# MySens-easyRS485-v002.net
KiCad netlist of a schematic drawn in EAGLE
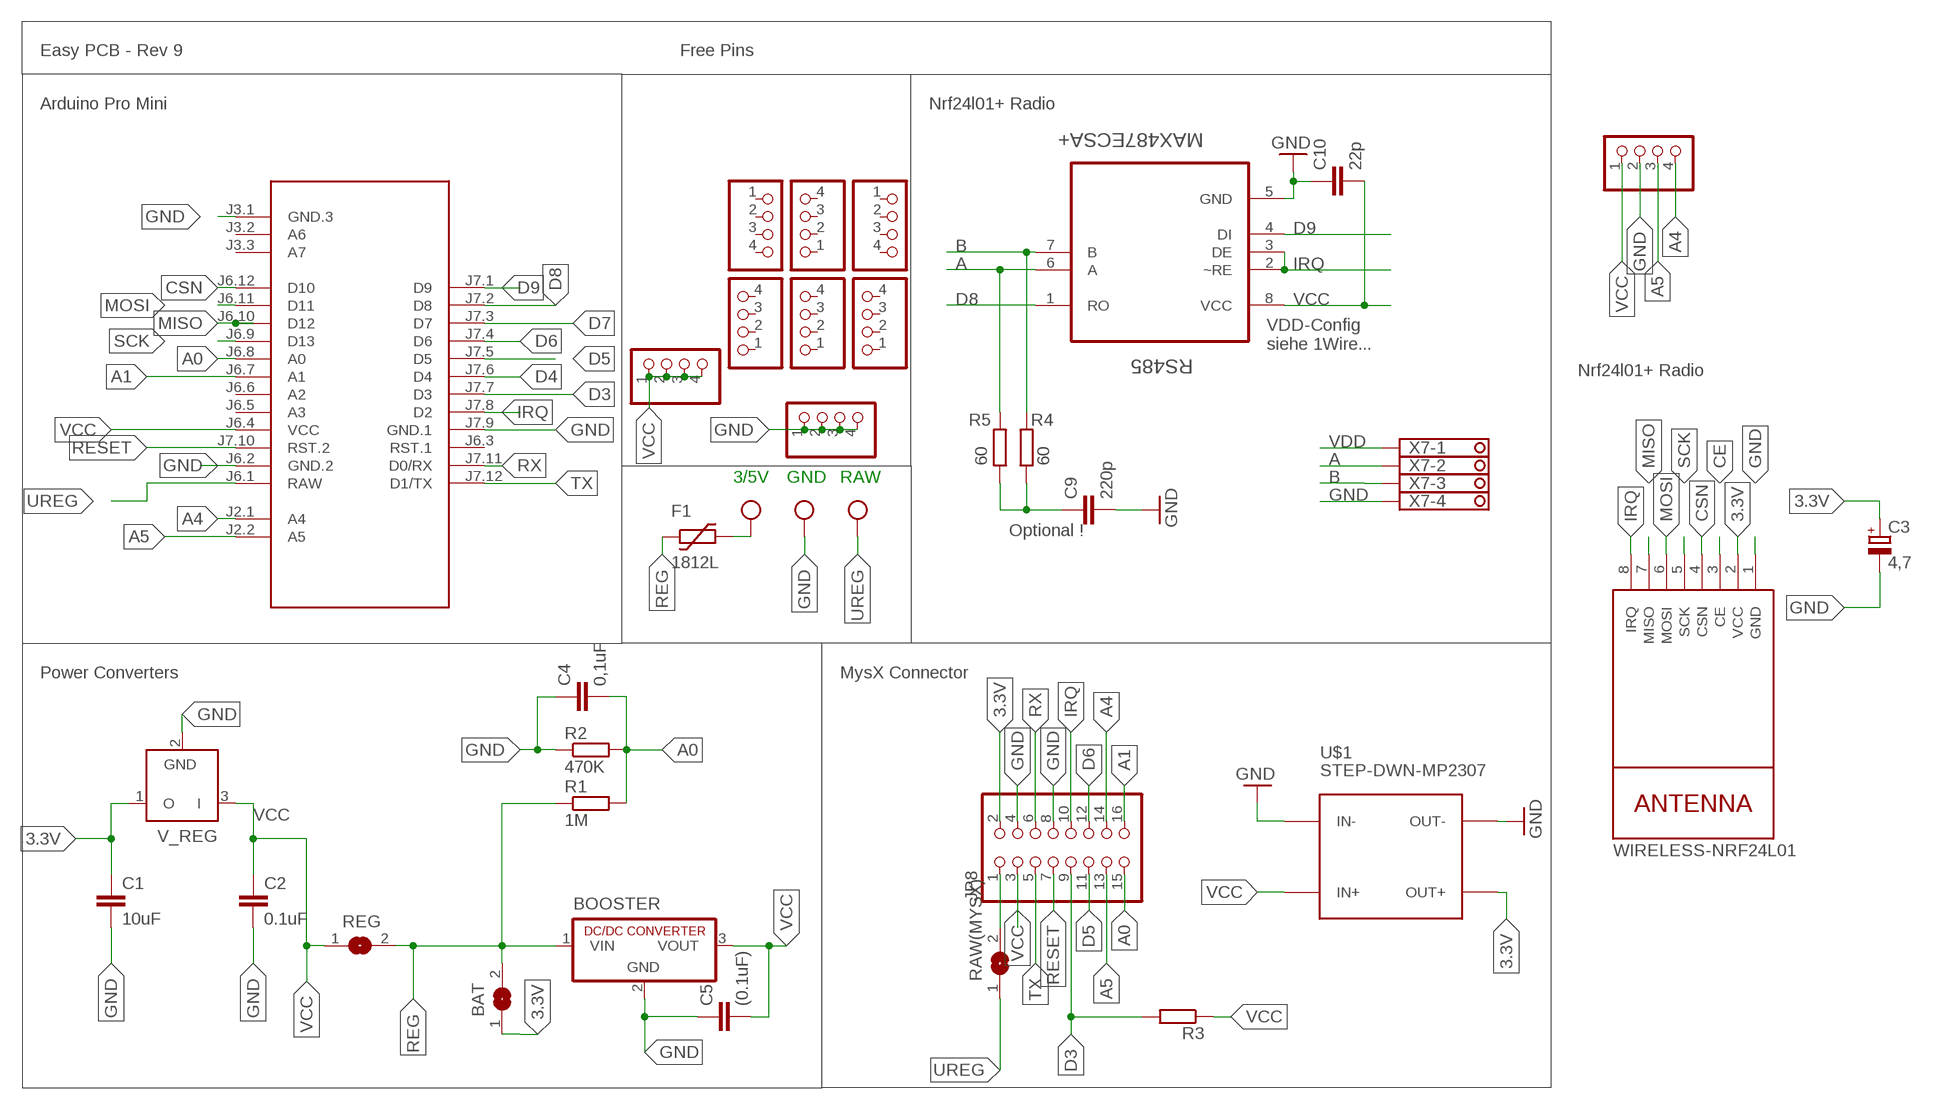
[diagram p0: schematic, sheet 1]

(export (version "E")
  (design (tool "Eeschema 10.0.6"))
  (components
    (comp (ref ".")
      (value "W237-103")
      (footprint "eagle-import:W237-103")
      (fields (field (name "MPN") "237-103"))
      (libsource (lib "eagle-import") (part "W237-103"))
    )
    (comp (ref "BAT") (value "SJ") (footprint "eagle-import:SJ") (libsource (lib "eagle-import") (part "SJ")))
    (comp (ref "BOOSTER")
      (value "R-78C1.8-1.0")
      (footprint "eagle-import:SIP3")
      (libsource (lib "eagle-import") (part "R-78C-1.01.8"))
    )
    (comp (ref "C1")
      (value "10uF")
      (footprint "eagle-import:C1210")
      (libsource (lib "eagle-import") (part "C-EUC1210"))
    )
    (comp (ref "C2")
      (value "0.1uF")
      (footprint "eagle-import:C1206")
      (libsource (lib "eagle-import") (part "C-EUC1206"))
    )
    (comp (ref "C3")
      (value "4,7")
      (footprint "eagle-import:SMC_C")
      (libsource (lib "eagle-import") (part "CPOL-EUSMCC"))
    )
    (comp (ref "C4")
      (value "0,1uF")
      (footprint "eagle-import:C1206")
      (libsource (lib "eagle-import") (part "C-EUC1206"))
    )
    (comp (ref "C5")
      (value "(0.1uF)")
      (footprint "eagle-import:C1206")
      (libsource (lib "eagle-import") (part "C-EUC1206"))
    )
    (comp (ref "C9")
      (value "220p")
      (footprint "eagle-import:C0805")
      (libsource (lib "eagle-import") (part "C-EUC0805"))
    )
    (comp (ref "C10")
      (value "22p")
      (footprint "eagle-import:C0805")
      (libsource (lib "eagle-import") (part "C-EUC0805"))
    )
    (comp (ref "F1")
      (value "1812L")
      (footprint "eagle-import:1812L")
      (libsource (lib "eagle-import") (part "1812L"))
    )
    (comp (ref "JP1")
      (value "PINHD-1X04_2.54-S")
      (footprint "eagle-import:1X04-S")
      (libsource (lib "eagle-import") (part "PINHD-1X04_2.54-S"))
    )
    (comp (ref "JP3")
      (value "PINHD-1X04_2.54-S")
      (footprint "eagle-import:1X04-S")
      (libsource (lib "eagle-import") (part "PINHD-1X04_2.54-S"))
    )
    (comp (ref "JP5")
      (value "PINHD-1X04_2.54-S")
      (footprint "eagle-import:1X04-S")
      (libsource (lib "eagle-import") (part "PINHD-1X04_2.54-S"))
    )
    (comp (ref "JP8")
      (value "PINHD-2X08_2.54")
      (footprint "eagle-import:2X08")
      (libsource (lib "eagle-import") (part "PINHD-2X08_2.54"))
    )
    (comp (ref "JP10")
      (value "PINHD-1X04_2.54-S")
      (footprint "eagle-import:1X04-S")
      (libsource (lib "eagle-import") (part "PINHD-1X04_2.54-S"))
    )
    (comp (ref "JP11")
      (value "PINHD-1X04_2.54-S")
      (footprint "eagle-import:1X04-S")
      (libsource (lib "eagle-import") (part "PINHD-1X04_2.54-S"))
    )
    (comp (ref "JP12")
      (value "PINHD-1X04_2.54-S")
      (footprint "eagle-import:1X04-S")
      (libsource (lib "eagle-import") (part "PINHD-1X04_2.54-S"))
    )
    (comp (ref "JP14")
      (value "PINHD-1X04_2.54-S")
      (footprint "eagle-import:1X04-S")
      (libsource (lib "eagle-import") (part "PINHD-1X04_2.54-S"))
    )
    (comp (ref "JP15")
      (value "PINHD-1X04_2.54-S")
      (footprint "eagle-import:1X04-S")
      (libsource (lib "eagle-import") (part "PINHD-1X04_2.54-S"))
    )
    (comp (ref "JP16")
      (value "PINHD-1X04_2.54-S")
      (footprint "eagle-import:1X04-S")
      (libsource (lib "eagle-import") (part "PINHD-1X04_2.54-S"))
    )
    (comp (ref "M1")
      (value "ARDUINO-PRO-MINI-3.3V#NP")
      (footprint "eagle-import:ARDUINO-PRO-MINI#NP")
      (libsource (lib "eagle-import") (part "ARDUINO-PRO-MINI-#NP3.3V"))
    )
    (comp (ref "NRF24L01+")
      (value "WIRELESS-NRF24L01")
      (footprint "eagle-import:WIRELESS-NRF24L01")
      (libsource (lib "eagle-import") (part "WIRELESS-NRF24L01"))
    )
    (comp (ref "R1")
      (value "1M")
      (footprint "eagle-import:R0805")
      (libsource (lib "eagle-import") (part "R-EU_R0805"))
    )
    (comp (ref "R2")
      (value "470K")
      (footprint "eagle-import:R0805")
      (libsource (lib "eagle-import") (part "R-EU_R0805"))
    )
    (comp (ref "R3")
      (value "R-EU_R0805")
      (footprint "eagle-import:R0805")
      (libsource (lib "eagle-import") (part "R-EU_R0805"))
    )
    (comp (ref "R4")
      (value "60")
      (footprint "eagle-import:R0805")
      (libsource (lib "eagle-import") (part "R-EU_R0805"))
    )
    (comp (ref "R5")
      (value "60")
      (footprint "eagle-import:R0805")
      (libsource (lib "eagle-import") (part "R-EU_R0805"))
    )
    (comp (ref "RAW(MYSX)")
      (value "SJ")
      (footprint "eagle-import:SJ")
      (libsource (lib "eagle-import") (part "SJ"))
    )
    (comp (ref "REG") (value "SJ") (footprint "eagle-import:SJ") (libsource (lib "eagle-import") (part "SJ")))
    (comp (ref "RS485")
      (value "MAX487ECSA+")
      (footprint "eagle-import:SOIC127P600X175-8N")
      (libsource (lib "eagle-import") (part "MAX487ECSA+"))
    )
    (comp (ref "U$1")
      (value "STEP-DWN-MP2307")
      (footprint "eagle-import:DC-DC-STEP-DOWN-MP2307")
      (libsource (lib "eagle-import") (part "DC-DC-STEP-DOWN-MP2307"))
    )
    (comp (ref "V_REG")
      (value "LP2950Z")
      (footprint "eagle-import:TO92")
      (libsource (lib "eagle-import") (part "LP2950Z"))
    )
    (comp (ref "X7")
      (value "1751264")
      (footprint "eagle-import:1751264")
      (libsource (lib "eagle-import") (part "1751264"))
    )
  )
  (nets
    (net (code "1") (name "/A") (class "Default")
      (node (ref "R5") (pin "2") (pinfunction "2_2") (pintype "passive"))
      (node (ref "RS485") (pin "6") (pinfunction "A_6") (pintype "bidirectional"))
      (node (ref "X7") (pin "2") (pinfunction "K_2") (pintype "passive"))
    )
    (net (code "2") (name "/B") (class "Default")
      (node (ref "R4") (pin "2") (pinfunction "2_2") (pintype "passive"))
      (node (ref "RS485") (pin "7") (pinfunction "B_7") (pintype "bidirectional"))
      (node (ref "X7") (pin "3") (pinfunction "K_3") (pintype "passive"))
    )
    (net (code "3") (name "/VDD") (class "Default")
      (node (ref "X7") (pin "1") (pinfunction "K_1") (pintype "passive"))
    )
    (net (code "4") (name "3.3V") (class "Default")
      (node (ref "BAT") (pin "1") (pinfunction "1_1") (pintype "passive"))
      (node (ref "C1") (pin "1") (pinfunction "1_1") (pintype "passive"))
      (node (ref "C3") (pin "+") (pinfunction "+_+") (pintype "passive"))
      (node (ref "JP8") (pin "2") (pinfunction "2_2") (pintype "passive"))
      (node (ref "NRF24L01+") (pin "2") (pinfunction "VCC_2") (pintype "power_in"))
      (node (ref "U$1") (pin "OUT+") (pinfunction "OUT+_OUT+") (pintype "bidirectional"))
      (node (ref "V_REG") (pin "1") (pinfunction "O_1") (pintype "input"))
    )
    (net (code "5") (name "A0") (class "Default")
      (node (ref "C4") (pin "2") (pinfunction "2_2") (pintype "passive"))
      (node (ref "JP8") (pin "15") (pinfunction "15_15") (pintype "passive"))
      (node (ref "M1") (pin "J6.8") (pinfunction "A0_J6.8") (pintype "bidirectional"))
      (node (ref "R1") (pin "2") (pinfunction "2_2") (pintype "passive"))
      (node (ref "R2") (pin "2") (pinfunction "2_2") (pintype "passive"))
    )
    (net (code "6") (name "A1") (class "Default")
      (node (ref "JP8") (pin "16") (pinfunction "16_16") (pintype "passive"))
      (node (ref "M1") (pin "J6.7") (pinfunction "A1_J6.7") (pintype "bidirectional"))
    )
    (net (code "7") (name "A4") (class "Default")
      (node (ref "JP10") (pin "4") (pinfunction "4_4") (pintype "passive"))
      (node (ref "JP8") (pin "14") (pinfunction "14_14") (pintype "passive"))
      (node (ref "M1") (pin "J2.1") (pinfunction "A4_J2.1") (pintype "bidirectional"))
    )
    (net (code "8") (name "A5") (class "Default")
      (node (ref "JP10") (pin "3") (pinfunction "3_3") (pintype "passive"))
      (node (ref "JP8") (pin "13") (pinfunction "13_13") (pintype "passive"))
      (node (ref "M1") (pin "J2.2") (pinfunction "A5_J2.2") (pintype "bidirectional"))
    )
    (net (code "9") (name "CE") (class "Default")
      (node (ref "NRF24L01+") (pin "3") (pinfunction "CE_3") (pintype "bidirectional"))
    )
    (net (code "10") (name "CSN") (class "Default")
      (node (ref "M1") (pin "J6.12") (pinfunction "D10_J6.12") (pintype "bidirectional"))
      (node (ref "NRF24L01+") (pin "4") (pinfunction "CSN_4") (pintype "bidirectional"))
    )
    (net (code "11") (name "D3") (class "Default")
      (node (ref "JP8") (pin "9") (pinfunction "9_9") (pintype "passive"))
      (node (ref "M1") (pin "J7.7") (pinfunction "D3_J7.7") (pintype "bidirectional"))
      (node (ref "R3") (pin "2") (pinfunction "2_2") (pintype "passive"))
    )
    (net (code "12") (name "D4") (class "Default")
      (node (ref "M1") (pin "J7.6") (pinfunction "D4_J7.6") (pintype "bidirectional"))
    )
    (net (code "13") (name "D5") (class "Default")
      (node (ref "JP8") (pin "11") (pinfunction "11_11") (pintype "passive"))
      (node (ref "M1") (pin "J7.5") (pinfunction "D5_J7.5") (pintype "bidirectional"))
    )
    (net (code "14") (name "D6") (class "Default")
      (node (ref "JP8") (pin "12") (pinfunction "12_12") (pintype "passive"))
      (node (ref "M1") (pin "J7.4") (pinfunction "D6_J7.4") (pintype "bidirectional"))
    )
    (net (code "15") (name "D7") (class "Default")
      (node (ref "M1") (pin "J7.3") (pinfunction "D7_J7.3") (pintype "bidirectional"))
    )
    (net (code "16") (name "D8") (class "Default")
      (node (ref "M1") (pin "J7.2") (pinfunction "D8_J7.2") (pintype "bidirectional"))
      (node (ref "RS485") (pin "1") (pinfunction "RO_1") (pintype "output"))
    )
    (net (code "17") (name "D9") (class "Default")
      (node (ref "M1") (pin "J7.1") (pinfunction "D9_J7.1") (pintype "bidirectional"))
      (node (ref "RS485") (pin "4") (pinfunction "DI_4") (pintype "input"))
    )
    (net (code "18") (name "GND") (class "Default")
      (node (ref ".") (pin "2") (pinfunction "KL_2") (pintype "passive"))
      (node (ref "BOOSTER") (pin "2") (pinfunction "GND_2") (pintype "passive"))
      (node (ref "C1") (pin "2") (pinfunction "2_2") (pintype "passive"))
      (node (ref "C10") (pin "1") (pinfunction "1_1") (pintype "passive"))
      (node (ref "C2") (pin "2") (pinfunction "2_2") (pintype "passive"))
      (node (ref "C3") (pin "-") (pinfunction "-_-") (pintype "passive"))
      (node (ref "C4") (pin "1") (pinfunction "1_1") (pintype "passive"))
      (node (ref "C5") (pin "1") (pinfunction "1_1") (pintype "passive"))
      (node (ref "C9") (pin "2") (pinfunction "2_2") (pintype "passive"))
      (node (ref "JP1") (pin "1") (pinfunction "1_1") (pintype "passive"))
      (node (ref "JP1") (pin "2") (pinfunction "2_2") (pintype "passive"))
      (node (ref "JP1") (pin "3") (pinfunction "3_3") (pintype "passive"))
      (node (ref "JP1") (pin "4") (pinfunction "4_4") (pintype "passive"))
      (node (ref "JP10") (pin "2") (pinfunction "2_2") (pintype "passive"))
      (node (ref "JP8") (pin "4") (pinfunction "4_4") (pintype "passive"))
      (node (ref "JP8") (pin "8") (pinfunction "8_8") (pintype "passive"))
      (node (ref "M1") (pin "J3.1") (pinfunction "GND.3_J3.1") (pintype "bidirectional"))
      (node (ref "M1") (pin "J6.2") (pinfunction "GND.2_J6.2") (pintype "power_in"))
      (node (ref "M1") (pin "J7.9") (pinfunction "GND.1_J7.9") (pintype "power_in"))
      (node (ref "NRF24L01+") (pin "1") (pinfunction "GND_1") (pintype "power_in"))
      (node (ref "R2") (pin "1") (pinfunction "1_1") (pintype "passive"))
      (node (ref "RS485") (pin "5") (pinfunction "GND_5") (pintype "passive"))
      (node (ref "U$1") (pin "IN-") (pinfunction "IN-_IN-") (pintype "bidirectional"))
      (node (ref "U$1") (pin "OUT-") (pinfunction "OUT-_OUT-") (pintype "bidirectional"))
      (node (ref "V_REG") (pin "2") (pinfunction "GND_2") (pintype "power_in"))
      (node (ref "X7") (pin "4") (pinfunction "K_4") (pintype "passive"))
    )
    (net (code "19") (name "IRQ") (class "Default")
      (node (ref "JP8") (pin "10") (pinfunction "10_10") (pintype "passive"))
      (node (ref "M1") (pin "J7.8") (pinfunction "D2_J7.8") (pintype "bidirectional"))
      (node (ref "NRF24L01+") (pin "8") (pinfunction "IRQ_8") (pintype "bidirectional"))
      (node (ref "RS485") (pin "2") (pinfunction "~{RE}_2") (pintype "input"))
      (node (ref "RS485") (pin "3") (pinfunction "DE_3") (pintype "input"))
    )
    (net (code "20") (name "MISO") (class "Default")
      (node (ref "M1") (pin "J6.10") (pinfunction "D12_J6.10") (pintype "bidirectional"))
      (node (ref "NRF24L01+") (pin "7") (pinfunction "MISO_7") (pintype "bidirectional"))
    )
    (net (code "21") (name "MOSI") (class "Default")
      (node (ref "M1") (pin "J6.11") (pinfunction "D11_J6.11") (pintype "bidirectional"))
      (node (ref "NRF24L01+") (pin "6") (pinfunction "MOSI_6") (pintype "bidirectional"))
    )
    (net (code "22") (name "Net-(.C-KL)") (class "Default")
      (node (ref ".") (pin "3") (pinfunction "KL_3") (pintype "passive"))
      (node (ref "F1") (pin "P$2") (pinfunction "2_P$2") (pintype "passive"))
    )
    (net (code "23") (name "Net-(C9-Pad1)") (class "Default")
      (node (ref "C9") (pin "1") (pinfunction "1_1") (pintype "passive"))
      (node (ref "R4") (pin "1") (pinfunction "1_1") (pintype "passive"))
      (node (ref "R5") (pin "1") (pinfunction "1_1") (pintype "passive"))
    )
    (net (code "24") (name "Net-(JP8-Pad1)") (class "Default")
      (node (ref "JP8") (pin "1") (pinfunction "1_1") (pintype "passive"))
      (node (ref "RAW(MYSX)") (pin "2") (pinfunction "2_2") (pintype "passive"))
    )
    (net (code "25") (name "REG") (class "Default")
      (node (ref "BAT") (pin "2") (pinfunction "2_2") (pintype "passive"))
      (node (ref "BOOSTER") (pin "1") (pinfunction "VIN_1") (pintype "passive"))
      (node (ref "F1") (pin "P$1") (pinfunction "1_P$1") (pintype "passive"))
      (node (ref "R1") (pin "1") (pinfunction "1_1") (pintype "passive"))
      (node (ref "REG") (pin "2") (pinfunction "2_2") (pintype "passive"))
    )
    (net (code "26") (name "RESET") (class "Default")
      (node (ref "JP8") (pin "7") (pinfunction "7_7") (pintype "passive"))
      (node (ref "M1") (pin "J7.10") (pinfunction "RST.2_J7.10") (pintype "bidirectional"))
    )
    (net (code "27") (name "RX") (class "Default")
      (node (ref "JP8") (pin "6") (pinfunction "6_6") (pintype "passive"))
      (node (ref "M1") (pin "J7.11") (pinfunction "D0/RX_J7.11") (pintype "bidirectional"))
    )
    (net (code "28") (name "SCK") (class "Default")
      (node (ref "M1") (pin "J6.9") (pinfunction "D13_J6.9") (pintype "bidirectional"))
      (node (ref "NRF24L01+") (pin "5") (pinfunction "SCK_5") (pintype "bidirectional"))
    )
    (net (code "29") (name "TX") (class "Default")
      (node (ref "JP8") (pin "5") (pinfunction "5_5") (pintype "passive"))
      (node (ref "M1") (pin "J7.12") (pinfunction "D1/TX_J7.12") (pintype "bidirectional"))
    )
    (net (code "30") (name "UREG") (class "Default")
      (node (ref ".") (pin "1") (pinfunction "KL_1") (pintype "passive"))
      (node (ref "M1") (pin "J6.1") (pinfunction "RAW_J6.1") (pintype "power_in"))
      (node (ref "RAW(MYSX)") (pin "1") (pinfunction "1_1") (pintype "passive"))
    )
    (net (code "31") (name "VCC") (class "Default")
      (node (ref "BOOSTER") (pin "3") (pinfunction "VOUT_3") (pintype "passive"))
      (node (ref "C10") (pin "2") (pinfunction "2_2") (pintype "passive"))
      (node (ref "C2") (pin "1") (pinfunction "1_1") (pintype "passive"))
      (node (ref "C5") (pin "2") (pinfunction "2_2") (pintype "passive"))
      (node (ref "JP10") (pin "1") (pinfunction "1_1") (pintype "passive"))
      (node (ref "JP3") (pin "1") (pinfunction "1_1") (pintype "passive"))
      (node (ref "JP3") (pin "2") (pinfunction "2_2") (pintype "passive"))
      (node (ref "JP3") (pin "3") (pinfunction "3_3") (pintype "passive"))
      (node (ref "JP3") (pin "4") (pinfunction "4_4") (pintype "passive"))
      (node (ref "JP8") (pin "3") (pinfunction "3_3") (pintype "passive"))
      (node (ref "M1") (pin "J6.4") (pinfunction "VCC_J6.4") (pintype "power_in"))
      (node (ref "R3") (pin "1") (pinfunction "1_1") (pintype "passive"))
      (node (ref "REG") (pin "1") (pinfunction "1_1") (pintype "passive"))
      (node (ref "RS485") (pin "8") (pinfunction "VCC_8") (pintype "power_in"))
      (node (ref "U$1") (pin "IN+") (pinfunction "IN+_IN+") (pintype "bidirectional"))
      (node (ref "V_REG") (pin "3") (pinfunction "I_3") (pintype "input"))
    )
    (net (code "32") (name "unconnected-(JP5-Pad1)") (class "Default")
      (node (ref "JP5") (pin "1") (pinfunction "1_1") (pintype "passive"))
    )
    (net (code "33") (name "unconnected-(JP5-Pad2)") (class "Default")
      (node (ref "JP5") (pin "2") (pinfunction "2_2") (pintype "passive"))
    )
    (net (code "34") (name "unconnected-(JP5-Pad3)") (class "Default")
      (node (ref "JP5") (pin "3") (pinfunction "3_3") (pintype "passive"))
    )
    (net (code "35") (name "unconnected-(JP5-Pad4)") (class "Default")
      (node (ref "JP5") (pin "4") (pinfunction "4_4") (pintype "passive"))
    )
    (net (code "36") (name "unconnected-(JP11-Pad1)") (class "Default")
      (node (ref "JP11") (pin "1") (pinfunction "1_1") (pintype "passive"))
    )
    (net (code "37") (name "unconnected-(JP11-Pad2)") (class "Default")
      (node (ref "JP11") (pin "2") (pinfunction "2_2") (pintype "passive"))
    )
    (net (code "38") (name "unconnected-(JP11-Pad3)") (class "Default")
      (node (ref "JP11") (pin "3") (pinfunction "3_3") (pintype "passive"))
    )
    (net (code "39") (name "unconnected-(JP11-Pad4)") (class "Default")
      (node (ref "JP11") (pin "4") (pinfunction "4_4") (pintype "passive"))
    )
    (net (code "40") (name "unconnected-(JP12-Pad1)") (class "Default")
      (node (ref "JP12") (pin "1") (pinfunction "1_1") (pintype "passive"))
    )
    (net (code "41") (name "unconnected-(JP12-Pad2)") (class "Default")
      (node (ref "JP12") (pin "2") (pinfunction "2_2") (pintype "passive"))
    )
    (net (code "42") (name "unconnected-(JP12-Pad3)") (class "Default")
      (node (ref "JP12") (pin "3") (pinfunction "3_3") (pintype "passive"))
    )
    (net (code "43") (name "unconnected-(JP12-Pad4)") (class "Default")
      (node (ref "JP12") (pin "4") (pinfunction "4_4") (pintype "passive"))
    )
    (net (code "44") (name "unconnected-(JP14-Pad1)") (class "Default")
      (node (ref "JP14") (pin "1") (pinfunction "1_1") (pintype "passive"))
    )
    (net (code "45") (name "unconnected-(JP14-Pad2)") (class "Default")
      (node (ref "JP14") (pin "2") (pinfunction "2_2") (pintype "passive"))
    )
    (net (code "46") (name "unconnected-(JP14-Pad3)") (class "Default")
      (node (ref "JP14") (pin "3") (pinfunction "3_3") (pintype "passive"))
    )
    (net (code "47") (name "unconnected-(JP14-Pad4)") (class "Default")
      (node (ref "JP14") (pin "4") (pinfunction "4_4") (pintype "passive"))
    )
    (net (code "48") (name "unconnected-(JP15-Pad1)") (class "Default")
      (node (ref "JP15") (pin "1") (pinfunction "1_1") (pintype "passive"))
    )
    (net (code "49") (name "unconnected-(JP15-Pad2)") (class "Default")
      (node (ref "JP15") (pin "2") (pinfunction "2_2") (pintype "passive"))
    )
    (net (code "50") (name "unconnected-(JP15-Pad3)") (class "Default")
      (node (ref "JP15") (pin "3") (pinfunction "3_3") (pintype "passive"))
    )
    (net (code "51") (name "unconnected-(JP15-Pad4)") (class "Default")
      (node (ref "JP15") (pin "4") (pinfunction "4_4") (pintype "passive"))
    )
    (net (code "52") (name "unconnected-(JP16-Pad1)") (class "Default")
      (node (ref "JP16") (pin "1") (pinfunction "1_1") (pintype "passive"))
    )
    (net (code "53") (name "unconnected-(JP16-Pad2)") (class "Default")
      (node (ref "JP16") (pin "2") (pinfunction "2_2") (pintype "passive"))
    )
    (net (code "54") (name "unconnected-(JP16-Pad3)") (class "Default")
      (node (ref "JP16") (pin "3") (pinfunction "3_3") (pintype "passive"))
    )
    (net (code "55") (name "unconnected-(JP16-Pad4)") (class "Default")
      (node (ref "JP16") (pin "4") (pinfunction "4_4") (pintype "passive"))
    )
    (net (code "56") (name "unconnected-(M1-A2-PadJ6.6)") (class "Default")
      (node (ref "M1") (pin "J6.6") (pinfunction "A2_J6.6") (pintype "bidirectional"))
    )
    (net (code "57") (name "unconnected-(M1-A3-PadJ6.5)") (class "Default")
      (node (ref "M1") (pin "J6.5") (pinfunction "A3_J6.5") (pintype "bidirectional"))
    )
    (net (code "58") (name "unconnected-(M1-A6-PadJ3.2)") (class "Default")
      (node (ref "M1") (pin "J3.2") (pinfunction "A6_J3.2") (pintype "bidirectional"))
    )
    (net (code "59") (name "unconnected-(M1-A7-PadJ3.3)") (class "Default")
      (node (ref "M1") (pin "J3.3") (pinfunction "A7_J3.3") (pintype "bidirectional"))
    )
    (net (code "60") (name "unconnected-(M1-RST.1-PadJ6.3)") (class "Default")
      (node (ref "M1") (pin "J6.3") (pinfunction "RST.1_J6.3") (pintype "bidirectional"))
    )
  )
)
